# eDP.net
KiCad netlist of a schematic drawn in Altium Designer
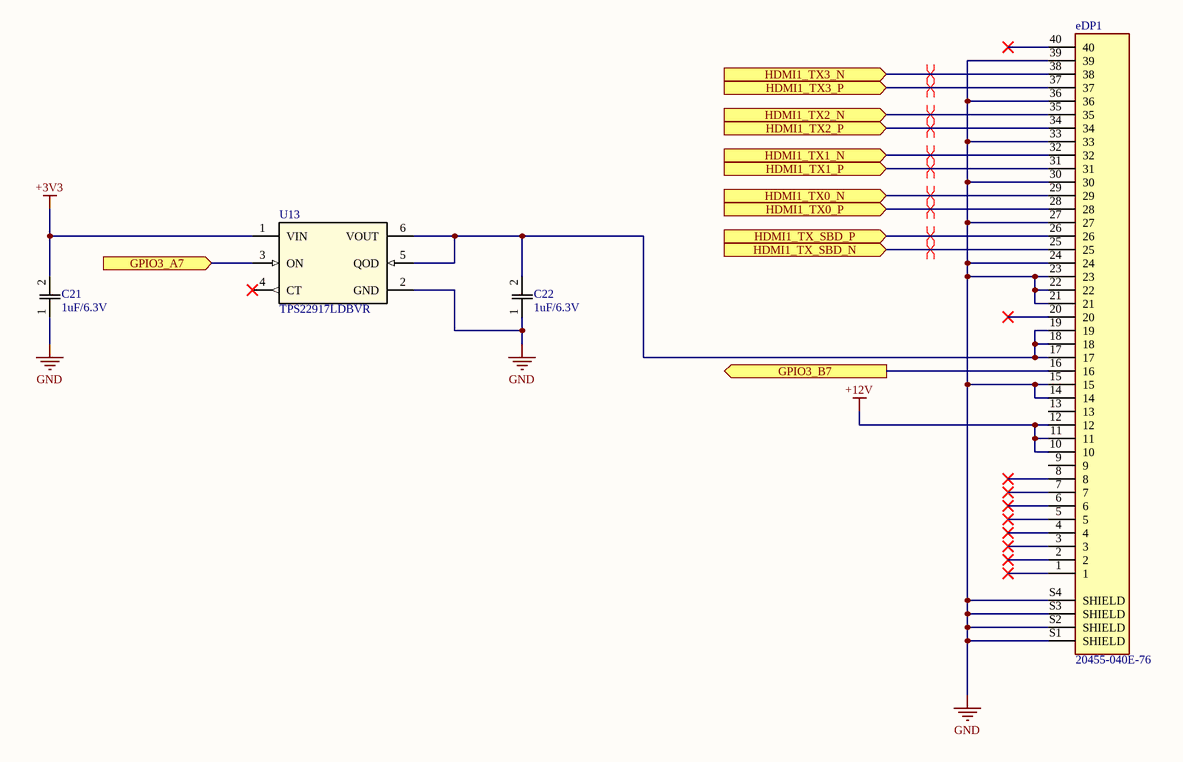
[diagram p0: eDP.SchDoc]

(export (version "E")
  (design (tool "Eeschema 10.0.6"))
  (components
    (comp (ref "C21")
      (value "1uF/6.3V")
      (footprint "SamacSys:C0805")
      (description "SMD Comm X7R")
      (fields (field (name "MANUFACTURER_PART_NUMBER") "C0805C105K9RACTU"))
      (libsource (lib "SamacSys") (part "C0805C105K9RACTU"))
    )
    (comp (ref "C22")
      (value "1uF/6.3V")
      (footprint "SamacSys:C0805")
      (description "SMD Comm X7R")
      (fields (field (name "MANUFACTURER_PART_NUMBER") "C0805C105K9RACTU"))
      (libsource (lib "SamacSys") (part "C0805C105K9RACTU"))
    )
    (comp (ref "eDP1")
      (value "20455-040E-76")
      (footprint "IPEX_20455-040E-76")
      (description "Conn Wire to Board RCP 40 POS 0.5mm Solder RA Side Entry SMDCABLINE® T/R")
      (fields (field (name "MANUFACTURER") "I-PEX"))
      (libsource (lib "20455-040E-76") (part "20455-040E-76"))
    )
    (comp (ref "U13")
      (value "TPS22917LDBVR")
      (footprint "DBV0006_L")
      (fields (field (name "MANUFACTURER") "Texas Instruments"))
      (libsource (lib "TPS22917LDBVR") (part "TPS22917LDBVR"))
    )
  )
  (nets
    (net (code "1") (name "+3V3") (class "Default")
      (node (ref "C21") (pin "2") (pinfunction "2_2") (pintype "passive"))
      (node (ref "U13") (pin "1") (pinfunction "VIN_1") (pintype "power_in"))
    )
    (net (code "2") (name "+12V") (class "Default")
      (node (ref "eDP1") (pin "10") (pinfunction "10_10") (pintype "passive"))
      (node (ref "eDP1") (pin "11") (pinfunction "11_11") (pintype "passive"))
      (node (ref "eDP1") (pin "12") (pinfunction "12_12") (pintype "passive"))
    )
    (net (code "3") (name "/GPIO3_A7") (class "Default")
      (node (ref "U13") (pin "3") (pinfunction "ON_3") (pintype "input"))
    )
    (net (code "4") (name "/GPIO3_B7") (class "Default")
      (node (ref "eDP1") (pin "16") (pinfunction "16_16") (pintype "passive"))
    )
    (net (code "5") (name "/HDMI1_TX0_N") (class "Default")
      (node (ref "eDP1") (pin "29") (pinfunction "29_29") (pintype "passive"))
    )
    (net (code "6") (name "/HDMI1_TX0_P") (class "Default")
      (node (ref "eDP1") (pin "28") (pinfunction "28_28") (pintype "passive"))
    )
    (net (code "7") (name "/HDMI1_TX1_N") (class "Default")
      (node (ref "eDP1") (pin "32") (pinfunction "32_32") (pintype "passive"))
    )
    (net (code "8") (name "/HDMI1_TX1_P") (class "Default")
      (node (ref "eDP1") (pin "31") (pinfunction "31_31") (pintype "passive"))
    )
    (net (code "9") (name "/HDMI1_TX2_N") (class "Default")
      (node (ref "eDP1") (pin "35") (pinfunction "35_35") (pintype "passive"))
    )
    (net (code "10") (name "/HDMI1_TX2_P") (class "Default")
      (node (ref "eDP1") (pin "34") (pinfunction "34_34") (pintype "passive"))
    )
    (net (code "11") (name "/HDMI1_TX3_N") (class "Default")
      (node (ref "eDP1") (pin "38") (pinfunction "38_38") (pintype "passive"))
    )
    (net (code "12") (name "/HDMI1_TX3_P") (class "Default")
      (node (ref "eDP1") (pin "37") (pinfunction "37_37") (pintype "passive"))
    )
    (net (code "13") (name "/HDMI1_TX_SBD_N") (class "Default")
      (node (ref "eDP1") (pin "25") (pinfunction "25_25") (pintype "passive"))
    )
    (net (code "14") (name "/HDMI1_TX_SBD_P") (class "Default")
      (node (ref "eDP1") (pin "26") (pinfunction "26_26") (pintype "passive"))
    )
    (net (code "15") (name "GND") (class "Default")
      (node (ref "C21") (pin "1") (pinfunction "1_1") (pintype "passive"))
      (node (ref "C22") (pin "1") (pinfunction "1_1") (pintype "passive"))
      (node (ref "U13") (pin "2") (pinfunction "GND_2") (pintype "passive"))
      (node (ref "eDP1") (pin "14") (pinfunction "14_14") (pintype "passive"))
      (node (ref "eDP1") (pin "15") (pinfunction "15_15") (pintype "passive"))
      (node (ref "eDP1") (pin "21") (pinfunction "21_21") (pintype "passive"))
      (node (ref "eDP1") (pin "22") (pinfunction "22_22") (pintype "passive"))
      (node (ref "eDP1") (pin "23") (pinfunction "23_23") (pintype "passive"))
      (node (ref "eDP1") (pin "24") (pinfunction "24_24") (pintype "passive"))
      (node (ref "eDP1") (pin "27") (pinfunction "27_27") (pintype "passive"))
      (node (ref "eDP1") (pin "30") (pinfunction "30_30") (pintype "passive"))
      (node (ref "eDP1") (pin "33") (pinfunction "33_33") (pintype "passive"))
      (node (ref "eDP1") (pin "36") (pinfunction "36_36") (pintype "passive"))
      (node (ref "eDP1") (pin "39") (pinfunction "39_39") (pintype "passive"))
      (node (ref "eDP1") (pin "S1") (pinfunction "SHIELD_S1") (pintype "passive"))
      (node (ref "eDP1") (pin "S2") (pinfunction "SHIELD_S2") (pintype "passive"))
      (node (ref "eDP1") (pin "S3") (pinfunction "SHIELD_S3") (pintype "passive"))
      (node (ref "eDP1") (pin "S4") (pinfunction "SHIELD_S4") (pintype "passive"))
    )
    (net (code "16") (name "Net-(U13-QOD)") (class "Default")
      (node (ref "C22") (pin "2") (pinfunction "2_2") (pintype "passive"))
      (node (ref "U13") (pin "5") (pinfunction "QOD_5") (pintype "input"))
      (node (ref "U13") (pin "6") (pinfunction "VOUT_6") (pintype "power_in"))
      (node (ref "eDP1") (pin "17") (pinfunction "17_17") (pintype "passive"))
      (node (ref "eDP1") (pin "18") (pinfunction "18_18") (pintype "passive"))
      (node (ref "eDP1") (pin "19") (pinfunction "19_19") (pintype "passive"))
    )
    (net (code "17") (name "unconnected-(U13-CT-Pad4)") (class "Default")
      (node (ref "U13") (pin "4") (pinfunction "CT_4") (pintype "output+no_connect"))
    )
    (net (code "18") (name "unconnected-(eDP1-Pad1)") (class "Default")
      (node (ref "eDP1") (pin "1") (pinfunction "1_1") (pintype "passive+no_connect"))
    )
    (net (code "19") (name "unconnected-(eDP1-Pad2)") (class "Default")
      (node (ref "eDP1") (pin "2") (pinfunction "2_2") (pintype "passive+no_connect"))
    )
    (net (code "20") (name "unconnected-(eDP1-Pad3)") (class "Default")
      (node (ref "eDP1") (pin "3") (pinfunction "3_3") (pintype "passive+no_connect"))
    )
    (net (code "21") (name "unconnected-(eDP1-Pad4)") (class "Default")
      (node (ref "eDP1") (pin "4") (pinfunction "4_4") (pintype "passive+no_connect"))
    )
    (net (code "22") (name "unconnected-(eDP1-Pad5)") (class "Default")
      (node (ref "eDP1") (pin "5") (pinfunction "5_5") (pintype "passive+no_connect"))
    )
    (net (code "23") (name "unconnected-(eDP1-Pad6)") (class "Default")
      (node (ref "eDP1") (pin "6") (pinfunction "6_6") (pintype "passive+no_connect"))
    )
    (net (code "24") (name "unconnected-(eDP1-Pad7)") (class "Default")
      (node (ref "eDP1") (pin "7") (pinfunction "7_7") (pintype "passive+no_connect"))
    )
    (net (code "25") (name "unconnected-(eDP1-Pad8)") (class "Default")
      (node (ref "eDP1") (pin "8") (pinfunction "8_8") (pintype "passive+no_connect"))
    )
    (net (code "26") (name "unconnected-(eDP1-Pad9)") (class "Default")
      (node (ref "eDP1") (pin "9") (pinfunction "9_9") (pintype "passive"))
    )
    (net (code "27") (name "unconnected-(eDP1-Pad13)") (class "Default")
      (node (ref "eDP1") (pin "13") (pinfunction "13_13") (pintype "passive"))
    )
    (net (code "28") (name "unconnected-(eDP1-Pad20)") (class "Default")
      (node (ref "eDP1") (pin "20") (pinfunction "20_20") (pintype "passive+no_connect"))
    )
    (net (code "29") (name "unconnected-(eDP1-Pad40)") (class "Default")
      (node (ref "eDP1") (pin "40") (pinfunction "40_40") (pintype "passive+no_connect"))
    )
  )
)
